# 7segement4digits1badidea-feathershield-m.net
KiCad netlist of a schematic drawn in EAGLE
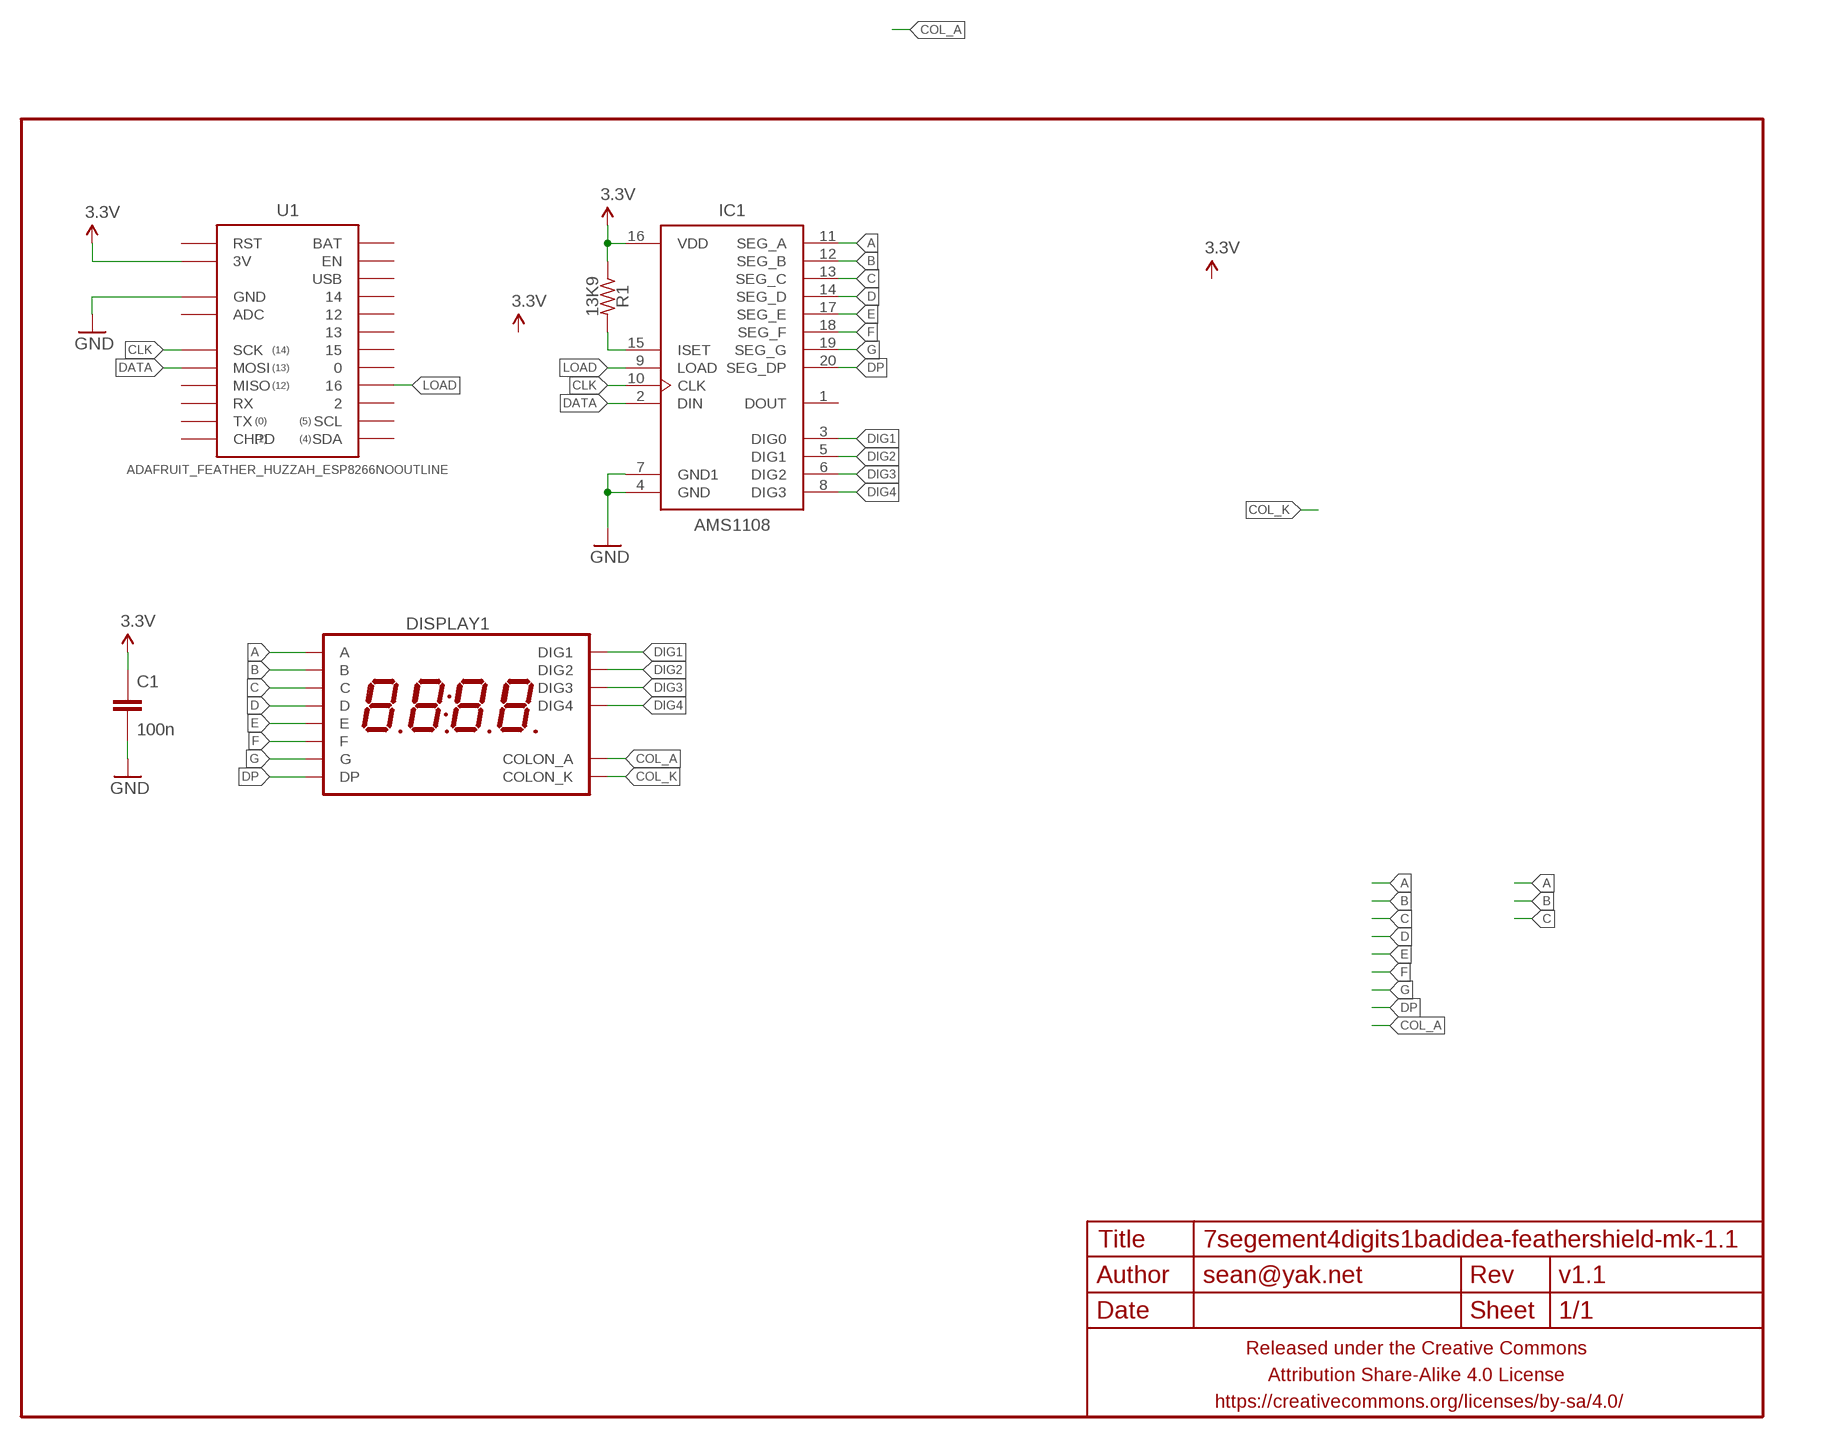
[diagram p0: schematic, sheet 1]

(export (version "E")
  (design (tool "Eeschema 10.0.6"))
  (components
    (comp (ref "C1")
      (value "100n")
      (footprint "eagle-import:C0603")
      (libsource (lib "eagle-import") (part "CAPACITOR-CERAMICC0603"))
    )
    (comp (ref "DISPLAY1")
      (value "7SEG_4DIGIT_COLON14.2MM-CC")
      (footprint "eagle-import:7SEG_4DIG_0.56IN_14MM_ADAFRUIT")
      (libsource (lib "eagle-import") (part "7SEG_4DIGIT_COLON14.2MM-CC"))
    )
    (comp (ref "FRAME1")
      (value "FRAME-LETTERNO_PACKAGE")
      (footprint "eagle-import:DUMMY")
      (fields (field (name "DESIGNER") "sean@yak.net") (field (name "VERSION") "v1.1"))
      (libsource (lib "eagle-import") (part "FRAME-LETTERNO_PACKAGE"))
    )
    (comp (ref "IC1")
      (value "AMS1108")
      (footprint "eagle-import:SO20W-NOSUCK")
      (libsource (lib "eagle-import") (part "AMS1108SOIC-20W"))
    )
    (comp (ref "R1")
      (value "13K9")
      (footprint "eagle-import:R0603")
      (libsource (lib "eagle-import") (part "RESISTORR0603"))
    )
    (comp (ref "U1")
      (value "ADAFRUIT_FEATHER_HUZZAH_ESP8266NOOUTLINE")
      (footprint "eagle-import:ADAFRUIT_FEATHER_HUZZAH_NOOUTLINE")
      (libsource (lib "eagle-import") (part "ADAFRUIT_FEATHER_HUZZAH_ESP8266NOOUTLINE"))
    )
  )
  (nets
    (net (code "1") (name "3.3V") (class "Default")
      (node (ref "C1") (pin "1") (pinfunction "1_1") (pintype "passive"))
      (node (ref "IC1") (pin "16") (pinfunction "VDD_16") (pintype "bidirectional"))
      (node (ref "R1") (pin "1") (pinfunction "1_1") (pintype "passive"))
      (node (ref "U1") (pin "3V") (pinfunction "3V_3V") (pintype "bidirectional"))
    )
    (net (code "2") (name "A") (class "Default")
      (node (ref "DISPLAY1") (pin "P$13") (pinfunction "A_P$13") (pintype "passive"))
      (node (ref "IC1") (pin "11") (pinfunction "SEG_A_11") (pintype "bidirectional"))
    )
    (net (code "3") (name "B") (class "Default")
      (node (ref "DISPLAY1") (pin "P$9") (pinfunction "B_P$9") (pintype "passive"))
      (node (ref "IC1") (pin "12") (pinfunction "SEG_B_12") (pintype "bidirectional"))
    )
    (net (code "4") (name "C") (class "Default")
      (node (ref "DISPLAY1") (pin "P$4") (pinfunction "C_P$4") (pintype "passive"))
      (node (ref "IC1") (pin "13") (pinfunction "SEG_C_13") (pintype "bidirectional"))
    )
    (net (code "5") (name "CLK") (class "Default")
      (node (ref "IC1") (pin "10") (pinfunction "CLK_10") (pintype "bidirectional"))
      (node (ref "U1") (pin "SCK") (pinfunction "SCK_SCK") (pintype "bidirectional"))
    )
    (net (code "6") (name "COL_A") (class "Default")
      (node (ref "DISPLAY1") (pin "P$8") (pinfunction "COLON_A_P$8") (pintype "passive"))
    )
    (net (code "7") (name "COL_K") (class "Default")
      (node (ref "DISPLAY1") (pin "P$7") (pinfunction "COLON_K_P$7") (pintype "passive"))
    )
    (net (code "8") (name "D") (class "Default")
      (node (ref "DISPLAY1") (pin "P$2") (pinfunction "D_P$2") (pintype "passive"))
      (node (ref "IC1") (pin "14") (pinfunction "SEG_D_14") (pintype "bidirectional"))
    )
    (net (code "9") (name "DATA") (class "Default")
      (node (ref "IC1") (pin "2") (pinfunction "DIN_2") (pintype "bidirectional"))
      (node (ref "U1") (pin "MOSI") (pinfunction "MOSI_MOSI") (pintype "bidirectional"))
    )
    (net (code "10") (name "DIG1") (class "Default")
      (node (ref "DISPLAY1") (pin "P$14") (pinfunction "DIG1_P$14") (pintype "passive"))
      (node (ref "IC1") (pin "3") (pinfunction "DIG0_3") (pintype "bidirectional"))
    )
    (net (code "11") (name "DIG2") (class "Default")
      (node (ref "DISPLAY1") (pin "P$11") (pinfunction "DIG2_P$11") (pintype "passive"))
      (node (ref "IC1") (pin "5") (pinfunction "DIG1_5") (pintype "bidirectional"))
    )
    (net (code "12") (name "DIG3") (class "Default")
      (node (ref "DISPLAY1") (pin "P$10") (pinfunction "DIG3_P$10") (pintype "passive"))
      (node (ref "IC1") (pin "6") (pinfunction "DIG2_6") (pintype "bidirectional"))
    )
    (net (code "13") (name "DIG4") (class "Default")
      (node (ref "DISPLAY1") (pin "P$6") (pinfunction "DIG4_P$6") (pintype "passive"))
      (node (ref "IC1") (pin "8") (pinfunction "DIG3_8") (pintype "bidirectional"))
    )
    (net (code "14") (name "DP") (class "Default")
      (node (ref "DISPLAY1") (pin "P$3") (pinfunction "DP_P$3") (pintype "passive"))
      (node (ref "IC1") (pin "20") (pinfunction "SEG_DP_20") (pintype "bidirectional"))
    )
    (net (code "15") (name "E") (class "Default")
      (node (ref "DISPLAY1") (pin "P$1") (pinfunction "E_P$1") (pintype "passive"))
      (node (ref "IC1") (pin "17") (pinfunction "SEG_E_17") (pintype "bidirectional"))
    )
    (net (code "16") (name "F") (class "Default")
      (node (ref "DISPLAY1") (pin "P$12") (pinfunction "F_P$12") (pintype "passive"))
      (node (ref "IC1") (pin "18") (pinfunction "SEG_F_18") (pintype "bidirectional"))
    )
    (net (code "17") (name "G") (class "Default")
      (node (ref "DISPLAY1") (pin "P$5") (pinfunction "G_P$5") (pintype "passive"))
      (node (ref "IC1") (pin "19") (pinfunction "SEG_G_19") (pintype "bidirectional"))
    )
    (net (code "18") (name "GND") (class "Default")
      (node (ref "C1") (pin "2") (pinfunction "2_2") (pintype "passive"))
      (node (ref "IC1") (pin "4") (pinfunction "GND_4") (pintype "bidirectional"))
      (node (ref "IC1") (pin "7") (pinfunction "GND1_7") (pintype "bidirectional"))
      (node (ref "U1") (pin "GND@0") (pinfunction "GND_GND@0") (pintype "bidirectional"))
    )
    (net (code "19") (name "LOAD") (class "Default")
      (node (ref "IC1") (pin "9") (pinfunction "LOAD_9") (pintype "bidirectional"))
      (node (ref "U1") (pin "16") (pinfunction "16_16") (pintype "bidirectional"))
    )
    (net (code "20") (name "Net-(IC1-ISET)") (class "Default")
      (node (ref "IC1") (pin "15") (pinfunction "ISET_15") (pintype "bidirectional"))
      (node (ref "R1") (pin "2") (pinfunction "2_2") (pintype "passive"))
    )
    (net (code "21") (name "unconnected-(IC1-DOUT-Pad1)") (class "Default")
      (node (ref "IC1") (pin "1") (pinfunction "DOUT_1") (pintype "bidirectional"))
    )
    (net (code "22") (name "unconnected-(U1-Pad0)") (class "Default")
      (node (ref "U1") (pin "0") (pinfunction "0_0") (pintype "bidirectional"))
    )
    (net (code "23") (name "unconnected-(U1-Pad2)") (class "Default")
      (node (ref "U1") (pin "2") (pinfunction "2_2") (pintype "bidirectional"))
    )
    (net (code "24") (name "unconnected-(U1-Pad12)") (class "Default")
      (node (ref "U1") (pin "12") (pinfunction "12_12") (pintype "bidirectional"))
    )
    (net (code "25") (name "unconnected-(U1-Pad13)") (class "Default")
      (node (ref "U1") (pin "13") (pinfunction "13_13") (pintype "bidirectional"))
    )
    (net (code "26") (name "unconnected-(U1-Pad14)") (class "Default")
      (node (ref "U1") (pin "14") (pinfunction "14_14") (pintype "bidirectional"))
    )
    (net (code "27") (name "unconnected-(U1-Pad15)") (class "Default")
      (node (ref "U1") (pin "15") (pinfunction "15_15") (pintype "bidirectional"))
    )
    (net (code "28") (name "unconnected-(U1-PadADC)") (class "Default")
      (node (ref "U1") (pin "ADC") (pinfunction "ADC_ADC") (pintype "bidirectional"))
    )
    (net (code "29") (name "unconnected-(U1-PadBAT)") (class "Default")
      (node (ref "U1") (pin "BAT") (pinfunction "BAT_BAT") (pintype "bidirectional"))
    )
    (net (code "30") (name "unconnected-(U1-PadCHPD)") (class "Default")
      (node (ref "U1") (pin "CHPD") (pinfunction "CHPD_CHPD") (pintype "bidirectional"))
    )
    (net (code "31") (name "unconnected-(U1-PadEN)") (class "Default")
      (node (ref "U1") (pin "EN") (pinfunction "EN_EN") (pintype "bidirectional"))
    )
    (net (code "32") (name "unconnected-(U1-PadMISO)") (class "Default")
      (node (ref "U1") (pin "MISO") (pinfunction "MISO_MISO") (pintype "bidirectional"))
    )
    (net (code "33") (name "unconnected-(U1-PadRST)") (class "Default")
      (node (ref "U1") (pin "RST") (pinfunction "RST_RST") (pintype "bidirectional"))
    )
    (net (code "34") (name "unconnected-(U1-PadRX)") (class "Default")
      (node (ref "U1") (pin "RX") (pinfunction "RX_RX") (pintype "bidirectional"))
    )
    (net (code "35") (name "unconnected-(U1-PadSCL)") (class "Default")
      (node (ref "U1") (pin "SCL") (pinfunction "SCL_SCL") (pintype "bidirectional"))
    )
    (net (code "36") (name "unconnected-(U1-PadSDA)") (class "Default")
      (node (ref "U1") (pin "SDA") (pinfunction "SDA_SDA") (pintype "bidirectional"))
    )
    (net (code "37") (name "unconnected-(U1-PadTX)") (class "Default")
      (node (ref "U1") (pin "TX") (pinfunction "TX_TX") (pintype "bidirectional"))
    )
    (net (code "38") (name "unconnected-(U1-PadUSB)") (class "Default")
      (node (ref "U1") (pin "USB") (pinfunction "USB_USB") (pintype "bidirectional"))
    )
  )
)
